# mLRS-rx-tx-E77-E22-dual-easysolder-v008.net
KiCad netlist of a schematic drawn in EAGLE
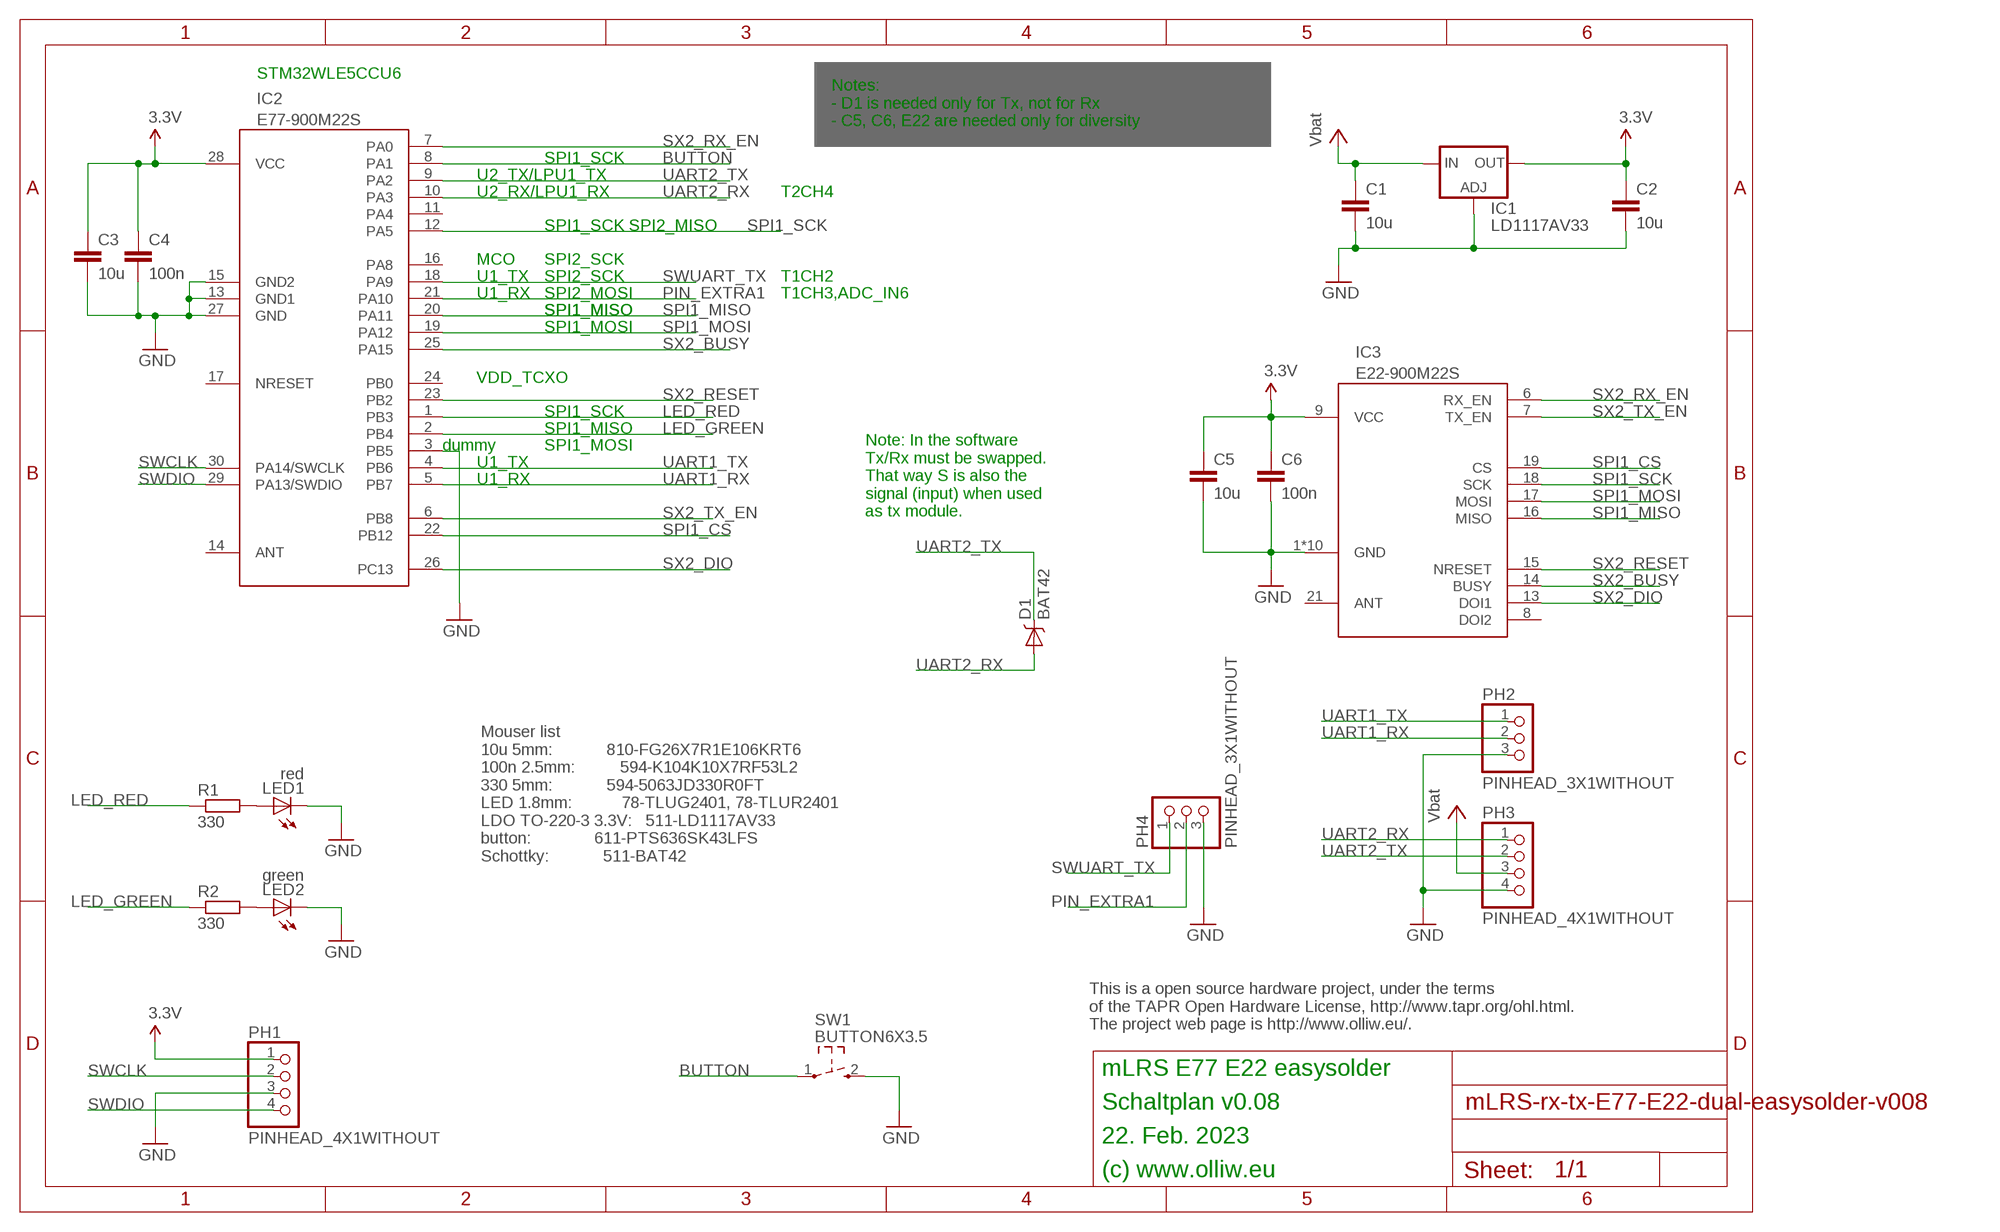
[diagram p0: schematic, sheet 1]

(export (version "E")
  (design (tool "Eeschema 10.0.6"))
  (components
    (comp (ref "C1")
      (value "10u")
      (footprint "eagle-import:C050-045X075")
      (libsource (lib "eagle-import") (part "C-EU050-045X075"))
    )
    (comp (ref "C2")
      (value "10u")
      (footprint "eagle-import:C050-045X075")
      (libsource (lib "eagle-import") (part "C-EU050-045X075"))
    )
    (comp (ref "C3")
      (value "10u")
      (footprint "eagle-import:C050-024X044")
      (libsource (lib "eagle-import") (part "C-EU050-024X044"))
    )
    (comp (ref "C4")
      (value "100n")
      (footprint "eagle-import:C025-024X044")
      (libsource (lib "eagle-import") (part "C-EU025-024X044"))
    )
    (comp (ref "C5")
      (value "10u")
      (footprint "eagle-import:C050-024X044")
      (libsource (lib "eagle-import") (part "C-EU050-024X044"))
    )
    (comp (ref "C6")
      (value "100n")
      (footprint "eagle-import:C025-024X044")
      (libsource (lib "eagle-import") (part "C-EU025-024X044"))
    )
    (comp (ref "D1")
      (value "BAT42")
      (footprint "eagle-import:D_7.5")
      (libsource (lib "eagle-import") (part "DIODE-SCHOTTKY7.62MM"))
    )
    (comp (ref "IC1")
      (value "LD1117AV33")
      (footprint "eagle-import:TO220L1")
      (libsource (lib "eagle-import") (part "LD117A?V33"))
    )
    (comp (ref "IC2")
      (value "E77-900M22S")
      (footprint "eagle-import:E77-900M22S")
      (libsource (lib "eagle-import") (part "E77-900M22S"))
    )
    (comp (ref "IC3")
      (value "E22-900M22S")
      (footprint "eagle-import:E22-900M22S")
      (libsource (lib "eagle-import") (part "E22-900M22S"))
    )
    (comp (ref "LED1")
      (value "red")
      (footprint "eagle-import:LED1.8MM")
      (libsource (lib "eagle-import") (part "LED1.8MM"))
    )
    (comp (ref "LED2")
      (value "green")
      (footprint "eagle-import:LED1.8MM")
      (libsource (lib "eagle-import") (part "LED1.8MM"))
    )
    (comp (ref "PH1")
      (value "PINHEAD_4X1WITHOUT")
      (footprint "eagle-import:PINHEAD_4X1_WO")
      (libsource (lib "eagle-import") (part "PINHEAD_4X1WITHOUT"))
    )
    (comp (ref "PH2")
      (value "PINHEAD_3X1WITHOUT")
      (footprint "eagle-import:PINHEAD_3X1_WO")
      (libsource (lib "eagle-import") (part "PINHEAD_3X1WITHOUT"))
    )
    (comp (ref "PH3")
      (value "PINHEAD_4X1WITHOUT")
      (footprint "eagle-import:PINHEAD_4X1_WO")
      (libsource (lib "eagle-import") (part "PINHEAD_4X1WITHOUT"))
    )
    (comp (ref "PH4")
      (value "PINHEAD_3X1WITHOUT")
      (footprint "eagle-import:PINHEAD_3X1_WO")
      (libsource (lib "eagle-import") (part "PINHEAD_3X1WITHOUT"))
    )
    (comp (ref "R1")
      (value "330")
      (footprint "eagle-import:R0204_6.25")
      (libsource (lib "eagle-import") (part "R_EUR0204/6.25"))
    )
    (comp (ref "R2")
      (value "330")
      (footprint "eagle-import:R0204_6.25")
      (libsource (lib "eagle-import") (part "R_EUR0204/6.25"))
    )
    (comp (ref "SW1")
      (value "BUTTON6X3.5")
      (footprint "eagle-import:BUTTON-THT")
      (libsource (lib "eagle-import") (part "BUTTON6X3.5"))
    )
  )
  (nets
    (net (code "1") (name "/BUTTON") (class "Default")
      (node (ref "IC2") (pin "8") (pinfunction "PA1_8") (pintype "bidirectional"))
      (node (ref "SW1") (pin "1") (pinfunction "1_1") (pintype "passive"))
    )
    (net (code "2") (name "/LED_GREEN") (class "Default")
      (node (ref "IC2") (pin "2") (pinfunction "PB4_2") (pintype "bidirectional"))
      (node (ref "R2") (pin "1") (pinfunction "1_1") (pintype "passive"))
    )
    (net (code "3") (name "/LED_RED") (class "Default")
      (node (ref "IC2") (pin "1") (pinfunction "PB3_1") (pintype "bidirectional"))
      (node (ref "R1") (pin "1") (pinfunction "1_1") (pintype "passive"))
    )
    (net (code "4") (name "/PIN_EXTRA1") (class "Default")
      (node (ref "IC2") (pin "21") (pinfunction "PA10_21") (pintype "bidirectional"))
      (node (ref "PH4") (pin "2") (pinfunction "3_2") (pintype "passive"))
    )
    (net (code "5") (name "/SPI1_CS") (class "Default")
      (node (ref "IC2") (pin "22") (pinfunction "PB12_22") (pintype "bidirectional"))
      (node (ref "IC3") (pin "19") (pinfunction "CS_19") (pintype "bidirectional"))
    )
    (net (code "6") (name "/SPI1_MISO") (class "Default")
      (node (ref "IC2") (pin "20") (pinfunction "PA11_20") (pintype "bidirectional"))
      (node (ref "IC3") (pin "16") (pinfunction "MISO_16") (pintype "bidirectional"))
    )
    (net (code "7") (name "/SPI1_MOSI") (class "Default")
      (node (ref "IC2") (pin "19") (pinfunction "PA12_19") (pintype "bidirectional"))
      (node (ref "IC3") (pin "17") (pinfunction "MOSI_17") (pintype "bidirectional"))
    )
    (net (code "8") (name "/SPI1_SCK") (class "Default")
      (node (ref "IC2") (pin "12") (pinfunction "PA5_12") (pintype "bidirectional"))
      (node (ref "IC3") (pin "18") (pinfunction "SCK_18") (pintype "bidirectional"))
    )
    (net (code "9") (name "/SWCLK") (class "Default")
      (node (ref "IC2") (pin "30") (pinfunction "PA14/SWCLK_30") (pintype "bidirectional"))
      (node (ref "PH1") (pin "2") (pinfunction "2_2") (pintype "passive"))
    )
    (net (code "10") (name "/SWDIO") (class "Default")
      (node (ref "IC2") (pin "29") (pinfunction "PA13/SWDIO_29") (pintype "bidirectional"))
      (node (ref "PH1") (pin "4") (pinfunction "4_4") (pintype "passive"))
    )
    (net (code "11") (name "/SWUART_TX") (class "Default")
      (node (ref "IC2") (pin "18") (pinfunction "PA9_18") (pintype "bidirectional"))
      (node (ref "PH4") (pin "1") (pinfunction "1_1") (pintype "passive"))
    )
    (net (code "12") (name "/SX2_BUSY") (class "Default")
      (node (ref "IC2") (pin "25") (pinfunction "PA15_25") (pintype "bidirectional"))
      (node (ref "IC3") (pin "14") (pinfunction "BUSY_14") (pintype "bidirectional"))
    )
    (net (code "13") (name "/SX2_DIO") (class "Default")
      (node (ref "IC2") (pin "26") (pinfunction "PC13_26") (pintype "bidirectional"))
      (node (ref "IC3") (pin "13") (pinfunction "DOI1_13") (pintype "bidirectional"))
    )
    (net (code "14") (name "/SX2_RESET") (class "Default")
      (node (ref "IC2") (pin "23") (pinfunction "PB2_23") (pintype "bidirectional"))
      (node (ref "IC3") (pin "15") (pinfunction "NRESET_15") (pintype "input"))
    )
    (net (code "15") (name "/SX2_RX_EN") (class "Default")
      (node (ref "IC2") (pin "7") (pinfunction "PA0_7") (pintype "bidirectional"))
      (node (ref "IC3") (pin "6") (pinfunction "RX_EN_6") (pintype "bidirectional"))
    )
    (net (code "16") (name "/SX2_TX_EN") (class "Default")
      (node (ref "IC2") (pin "6") (pinfunction "PB8_6") (pintype "bidirectional"))
      (node (ref "IC3") (pin "7") (pinfunction "TX_EN_7") (pintype "bidirectional"))
    )
    (net (code "17") (name "/UART1_RX") (class "Default")
      (node (ref "IC2") (pin "5") (pinfunction "PB7_5") (pintype "bidirectional"))
      (node (ref "PH2") (pin "2") (pinfunction "3_2") (pintype "passive"))
    )
    (net (code "18") (name "/UART1_TX") (class "Default")
      (node (ref "IC2") (pin "4") (pinfunction "PB6_4") (pintype "bidirectional"))
      (node (ref "PH2") (pin "1") (pinfunction "1_1") (pintype "passive"))
    )
    (net (code "19") (name "/UART2_RX") (class "Default")
      (node (ref "D1") (pin "A") (pinfunction "A_A") (pintype "passive"))
      (node (ref "IC2") (pin "10") (pinfunction "PA3_10") (pintype "bidirectional"))
      (node (ref "PH3") (pin "1") (pinfunction "1_1") (pintype "passive"))
    )
    (net (code "20") (name "/UART2_TX") (class "Default")
      (node (ref "D1") (pin "C") (pinfunction "C_C") (pintype "passive"))
      (node (ref "IC2") (pin "9") (pinfunction "PA2_9") (pintype "bidirectional"))
      (node (ref "PH3") (pin "2") (pinfunction "2_2") (pintype "passive"))
    )
    (net (code "21") (name "3.3V") (class "Default")
      (node (ref "C2") (pin "1") (pinfunction "1_1") (pintype "passive"))
      (node (ref "C3") (pin "1") (pinfunction "1_1") (pintype "passive"))
      (node (ref "C4") (pin "1") (pinfunction "1_1") (pintype "passive"))
      (node (ref "C5") (pin "1") (pinfunction "1_1") (pintype "passive"))
      (node (ref "C6") (pin "1") (pinfunction "1_1") (pintype "passive"))
      (node (ref "IC1") (pin "2") (pinfunction "OUT_2") (pintype "passive"))
      (node (ref "IC2") (pin "28") (pinfunction "VCC_28") (pintype "power_in"))
      (node (ref "IC3") (pin "9") (pinfunction "VCC_9") (pintype "power_in"))
      (node (ref "PH1") (pin "1") (pinfunction "1_1") (pintype "passive"))
    )
    (net (code "22") (name "GND") (class "Default")
      (node (ref "C1") (pin "2") (pinfunction "2_2") (pintype "passive"))
      (node (ref "C2") (pin "2") (pinfunction "2_2") (pintype "passive"))
      (node (ref "C3") (pin "2") (pinfunction "2_2") (pintype "passive"))
      (node (ref "C4") (pin "2") (pinfunction "2_2") (pintype "passive"))
      (node (ref "C5") (pin "2") (pinfunction "2_2") (pintype "passive"))
      (node (ref "C6") (pin "2") (pinfunction "2_2") (pintype "passive"))
      (node (ref "IC1") (pin "1") (pinfunction "ADJ_1") (pintype "input"))
      (node (ref "IC2") (pin "13") (pinfunction "GND1_13") (pintype "power_in"))
      (node (ref "IC2") (pin "15") (pinfunction "GND2_15") (pintype "power_in"))
      (node (ref "IC2") (pin "27") (pinfunction "GND_27") (pintype "power_in"))
      (node (ref "IC2") (pin "3") (pinfunction "PB5_3") (pintype "bidirectional"))
      (node (ref "IC3") (pin "1") (pinfunction "GND_1") (pintype "power_in"))
      (node (ref "IC3") (pin "10") (pinfunction "GND_10") (pintype "power_in"))
      (node (ref "IC3") (pin "11") (pinfunction "GND_11") (pintype "power_in"))
      (node (ref "IC3") (pin "12") (pinfunction "GND_12") (pintype "power_in"))
      (node (ref "IC3") (pin "2") (pinfunction "GND_2") (pintype "power_in"))
      (node (ref "IC3") (pin "20") (pinfunction "GND_20") (pintype "power_in"))
      (node (ref "IC3") (pin "22") (pinfunction "GND_22") (pintype "power_in"))
      (node (ref "IC3") (pin "3") (pinfunction "GND_3") (pintype "power_in"))
      (node (ref "IC3") (pin "4") (pinfunction "GND_4") (pintype "power_in"))
      (node (ref "IC3") (pin "5") (pinfunction "GND_5") (pintype "power_in"))
      (node (ref "LED1") (pin "K") (pinfunction "C_K") (pintype "passive"))
      (node (ref "LED2") (pin "K") (pinfunction "C_K") (pintype "passive"))
      (node (ref "PH1") (pin "3") (pinfunction "3_3") (pintype "passive"))
      (node (ref "PH2") (pin "3") (pinfunction "5_3") (pintype "passive"))
      (node (ref "PH3") (pin "4") (pinfunction "4_4") (pintype "passive"))
      (node (ref "PH4") (pin "3") (pinfunction "5_3") (pintype "passive"))
      (node (ref "SW1") (pin "2") (pinfunction "3_2") (pintype "passive"))
    )
    (net (code "23") (name "Net-(LED1-PadA)") (class "Default")
      (node (ref "LED1") (pin "A") (pinfunction "A_A") (pintype "passive"))
      (node (ref "R1") (pin "2") (pinfunction "2_2") (pintype "passive"))
    )
    (net (code "24") (name "Net-(LED2-PadA)") (class "Default")
      (node (ref "LED2") (pin "A") (pinfunction "A_A") (pintype "passive"))
      (node (ref "R2") (pin "2") (pinfunction "2_2") (pintype "passive"))
    )
    (net (code "25") (name "Vbat") (class "Default")
      (node (ref "C1") (pin "1") (pinfunction "1_1") (pintype "passive"))
      (node (ref "IC1") (pin "3") (pinfunction "IN_3") (pintype "input"))
      (node (ref "PH3") (pin "3") (pinfunction "3_3") (pintype "passive"))
    )
    (net (code "26") (name "unconnected-(IC2-ANT-Pad14)") (class "Default")
      (node (ref "IC2") (pin "14") (pinfunction "ANT_14") (pintype "bidirectional"))
    )
    (net (code "27") (name "unconnected-(IC2-NRESET-Pad17)") (class "Default")
      (node (ref "IC2") (pin "17") (pinfunction "NRESET_17") (pintype "input"))
    )
    (net (code "28") (name "unconnected-(IC2-PA4-Pad11)") (class "Default")
      (node (ref "IC2") (pin "11") (pinfunction "PA4_11") (pintype "bidirectional"))
    )
    (net (code "29") (name "unconnected-(IC2-PA8-Pad16)") (class "Default")
      (node (ref "IC2") (pin "16") (pinfunction "PA8_16") (pintype "bidirectional"))
    )
    (net (code "30") (name "unconnected-(IC2-PB0-Pad24)") (class "Default")
      (node (ref "IC2") (pin "24") (pinfunction "PB0_24") (pintype "bidirectional"))
    )
    (net (code "31") (name "unconnected-(IC3-ANT-Pad21)") (class "Default")
      (node (ref "IC3") (pin "21") (pinfunction "ANT_21") (pintype "bidirectional"))
    )
    (net (code "32") (name "unconnected-(IC3-DOI2-Pad8)") (class "Default")
      (node (ref "IC3") (pin "8") (pinfunction "DOI2_8") (pintype "bidirectional"))
    )
  )
)
